# ecu2.net
KiCad netlist of a schematic drawn in EAGLE
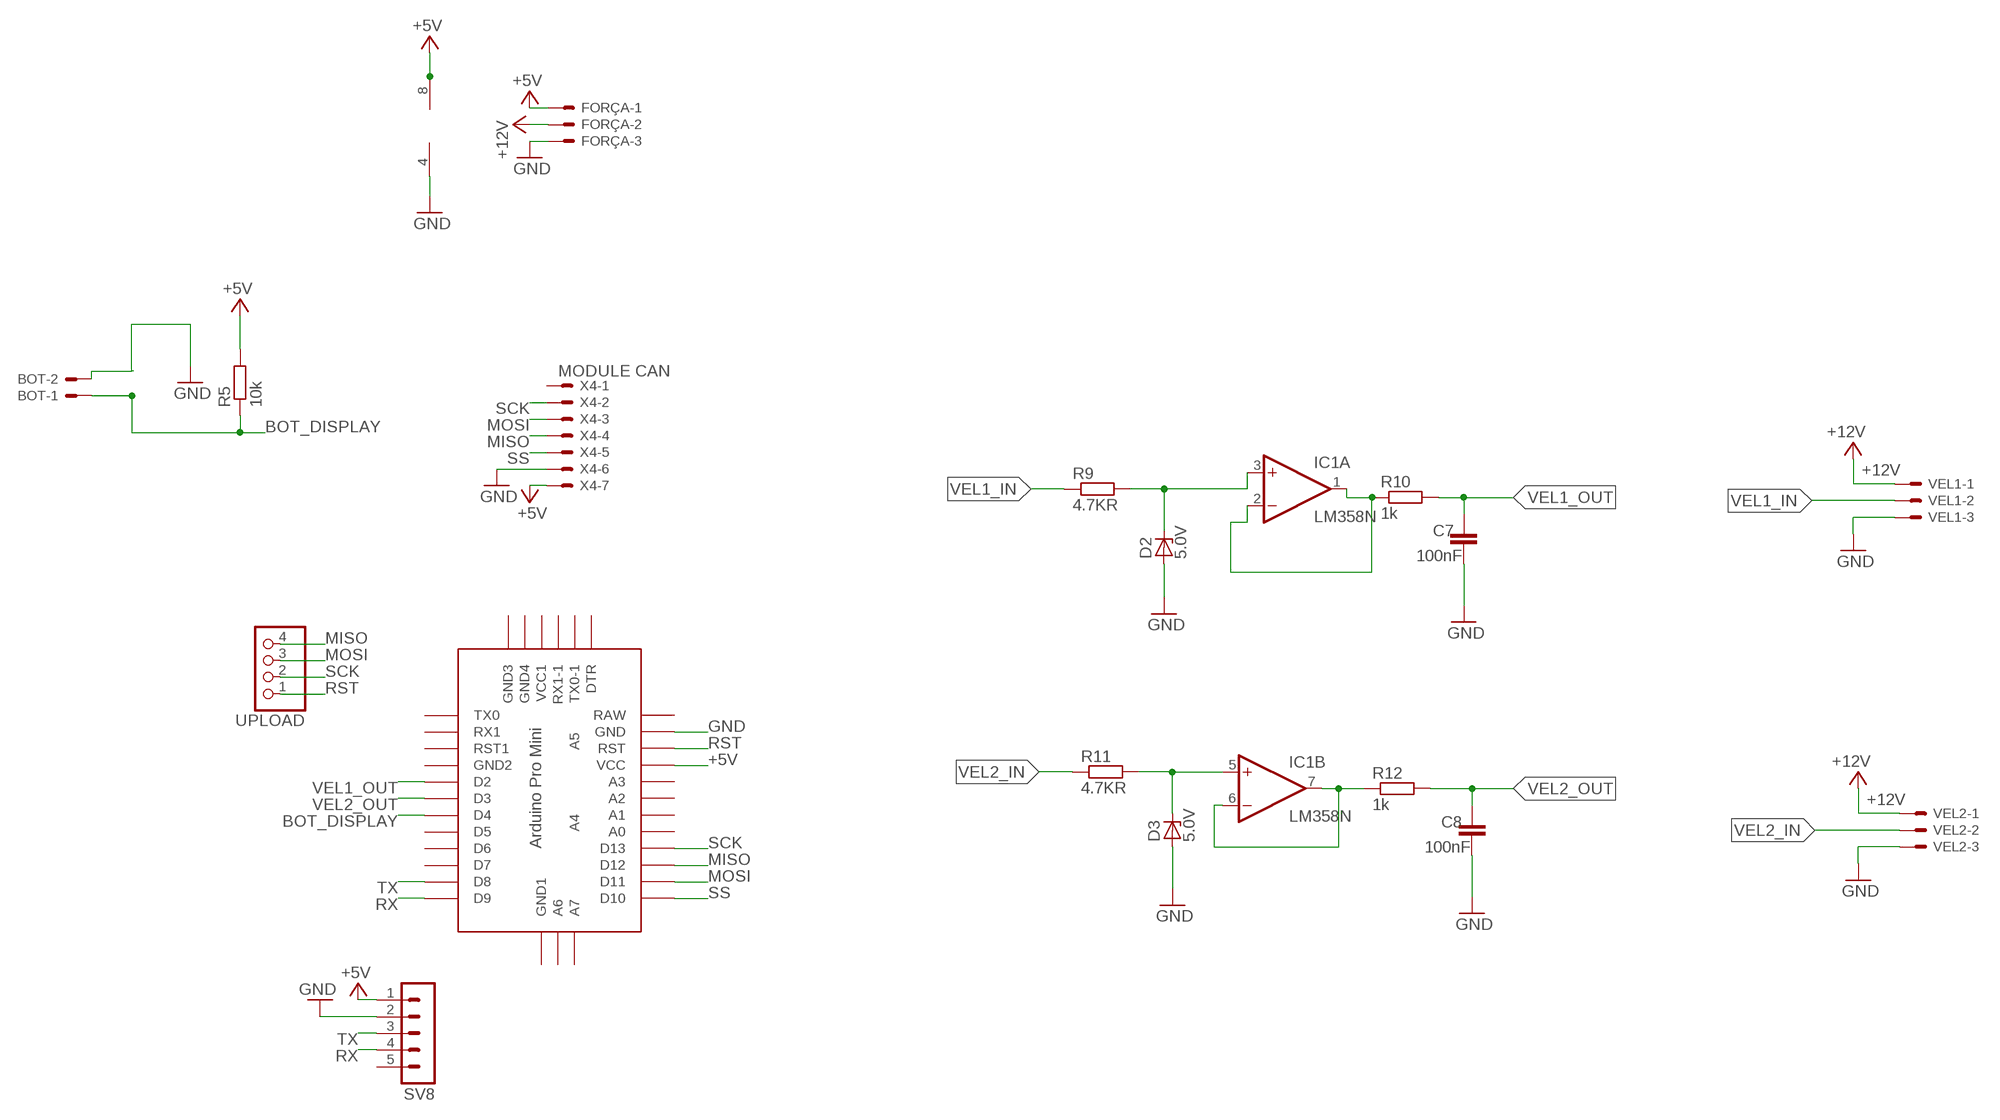
[diagram p0: schematic, sheet 1]

(export (version "E")
  (design (tool "Eeschema 10.0.6"))
  (components
    (comp (ref "BOT")
      (value "RPM")
      (footprint "eagle-import:22-23-2021")
      (fields (field (name "MF") "MOLEX") (field (name "MPN") "22-23-2021"))
      (libsource (lib "eagle-import") (part "22-23-2021"))
    )
    (comp (ref "C7")
      (value "100nF")
      (footprint "eagle-import:C5B2.5")
      (libsource (lib "eagle-import") (part "C5/2.5"))
    )
    (comp (ref "C8")
      (value "100nF")
      (footprint "eagle-import:C5B2.5")
      (libsource (lib "eagle-import") (part "C5/2.5"))
    )
    (comp (ref "D2")
      (value "5.0V")
      (footprint "eagle-import:DO34Z7")
      (libsource (lib "eagle-import") (part "ZENER-DIODEDO34-7"))
    )
    (comp (ref "D3")
      (value "5.0V")
      (footprint "eagle-import:DO34Z7")
      (libsource (lib "eagle-import") (part "ZENER-DIODEDO34-7"))
    )
    (comp (ref "FORÇA")
      (value "FORÇA")
      (footprint "eagle-import:22-23-2031")
      (fields (field (name "MF") "MOLEX") (field (name "MPN") "22-23-2031"))
      (libsource (lib "eagle-import") (part "22-23-2031"))
    )
    (comp (ref "IC1")
      (value "LM358N")
      (footprint "eagle-import:DIL08")
      (libsource (lib "eagle-import") (part "LM358N"))
    )
    (comp (ref "R5")
      (value "10k")
      (footprint "eagle-import:0207_7")
      (libsource (lib "eagle-import") (part "R-EU_0207/7"))
    )
    (comp (ref "R9")
      (value "4.7KR")
      (footprint "eagle-import:0207_7")
      (libsource (lib "eagle-import") (part "R-EU_0207/7"))
    )
    (comp (ref "R10")
      (value "1k")
      (footprint "eagle-import:0207_7")
      (libsource (lib "eagle-import") (part "R-EU_0207/7"))
    )
    (comp (ref "R11")
      (value "4.7KR")
      (footprint "eagle-import:0207_7")
      (libsource (lib "eagle-import") (part "R-EU_0207/7"))
    )
    (comp (ref "R12")
      (value "1k")
      (footprint "eagle-import:0207_7")
      (libsource (lib "eagle-import") (part "R-EU_0207/7"))
    )
    (comp (ref "SV8")
      (value "MA05-1")
      (footprint "eagle-import:MA05-1")
      (libsource (lib "eagle-import") (part "MA05-1"))
    )
    (comp (ref "U$1")
      (value "ABK-PRO-MINI")
      (footprint "eagle-import:ABK-PRO-MINI")
      (libsource (lib "eagle-import") (part "ABK-PRO-MINI"))
    )
    (comp (ref "UPLOAD")
      (value "PINHD-1X4")
      (footprint "eagle-import:1X04")
      (libsource (lib "eagle-import") (part "PINHD-1X4"))
    )
    (comp (ref "VEL1")
      (value "COMB 1")
      (footprint "eagle-import:22-23-2031")
      (fields (field (name "MF") "MOLEX") (field (name "MPN") "22-23-2031"))
      (libsource (lib "eagle-import") (part "22-23-2031"))
    )
    (comp (ref "VEL2")
      (value "COMB 2")
      (footprint "eagle-import:22-23-2031")
      (fields (field (name "MF") "MOLEX") (field (name "MPN") "22-23-2031"))
      (libsource (lib "eagle-import") (part "22-23-2031"))
    )
    (comp (ref "X4")
      (value "MODULE CAN")
      (footprint "eagle-import:22-23-2071")
      (fields (field (name "MF") "MOLEX") (field (name "MPN") "22-23-2071"))
      (libsource (lib "eagle-import") (part "22-23-2071"))
    )
  )
  (nets
    (net (code "1") (name "+5V") (class "Default")
      (node (ref "FORÇA") (pin "1") (pinfunction "S_1") (pintype "passive"))
      (node (ref "IC1") (pin "8") (pinfunction "V+_8") (pintype "power_in"))
      (node (ref "R5") (pin "2") (pinfunction "2_2") (pintype "passive"))
      (node (ref "SV8") (pin "1") (pinfunction "1_1") (pintype "passive"))
      (node (ref "U$1") (pin "VCC") (pinfunction "VCC_VCC") (pintype "bidirectional"))
      (node (ref "X4") (pin "7") (pinfunction "S_7") (pintype "passive"))
    )
    (net (code "2") (name "+12V") (class "Default")
      (node (ref "FORÇA") (pin "2") (pinfunction "S_2") (pintype "passive"))
      (node (ref "VEL1") (pin "1") (pinfunction "S_1") (pintype "passive"))
      (node (ref "VEL2") (pin "1") (pinfunction "S_1") (pintype "passive"))
    )
    (net (code "3") (name "/BOT_DISPLAY") (class "Default")
      (node (ref "BOT") (pin "1") (pinfunction "S_1") (pintype "passive"))
      (node (ref "R5") (pin "1") (pinfunction "1_1") (pintype "passive"))
      (node (ref "U$1") (pin "D4") (pinfunction "D4_D4") (pintype "bidirectional"))
    )
    (net (code "4") (name "/MISO") (class "Default")
      (node (ref "U$1") (pin "D12") (pinfunction "D12_D12") (pintype "bidirectional"))
      (node (ref "UPLOAD") (pin "4") (pinfunction "4_4") (pintype "passive"))
      (node (ref "X4") (pin "4") (pinfunction "S_4") (pintype "passive"))
    )
    (net (code "5") (name "/MOSI") (class "Default")
      (node (ref "U$1") (pin "D11") (pinfunction "D11_D11") (pintype "bidirectional"))
      (node (ref "UPLOAD") (pin "3") (pinfunction "3_3") (pintype "passive"))
      (node (ref "X4") (pin "3") (pinfunction "S_3") (pintype "passive"))
    )
    (net (code "6") (name "/RST") (class "Default")
      (node (ref "U$1") (pin "RST") (pinfunction "RST_RST") (pintype "bidirectional"))
      (node (ref "UPLOAD") (pin "1") (pinfunction "1_1") (pintype "passive"))
    )
    (net (code "7") (name "/RX") (class "Default")
      (node (ref "SV8") (pin "4") (pinfunction "4_4") (pintype "passive"))
      (node (ref "U$1") (pin "D9") (pinfunction "D9_D9") (pintype "bidirectional"))
    )
    (net (code "8") (name "/SCK") (class "Default")
      (node (ref "U$1") (pin "D13") (pinfunction "D13_D13") (pintype "bidirectional"))
      (node (ref "UPLOAD") (pin "2") (pinfunction "2_2") (pintype "passive"))
      (node (ref "X4") (pin "2") (pinfunction "S_2") (pintype "passive"))
    )
    (net (code "9") (name "/SS") (class "Default")
      (node (ref "U$1") (pin "D10") (pinfunction "D10_D10") (pintype "bidirectional"))
      (node (ref "X4") (pin "5") (pinfunction "S_5") (pintype "passive"))
    )
    (net (code "10") (name "/TX") (class "Default")
      (node (ref "SV8") (pin "3") (pinfunction "3_3") (pintype "passive"))
      (node (ref "U$1") (pin "D8") (pinfunction "D8_D8") (pintype "bidirectional"))
    )
    (net (code "11") (name "GND") (class "Default")
      (node (ref "BOT") (pin "2") (pinfunction "S_2") (pintype "passive"))
      (node (ref "C7") (pin "1") (pinfunction "1_1") (pintype "passive"))
      (node (ref "C8") (pin "1") (pinfunction "1_1") (pintype "passive"))
      (node (ref "D2") (pin "A") (pinfunction "A_A") (pintype "passive"))
      (node (ref "D3") (pin "A") (pinfunction "A_A") (pintype "passive"))
      (node (ref "FORÇA") (pin "3") (pinfunction "S_3") (pintype "passive"))
      (node (ref "IC1") (pin "4") (pinfunction "V-_4") (pintype "power_in"))
      (node (ref "SV8") (pin "2") (pinfunction "2_2") (pintype "passive"))
      (node (ref "U$1") (pin "GND") (pinfunction "GND_GND") (pintype "bidirectional"))
      (node (ref "VEL1") (pin "3") (pinfunction "S_3") (pintype "passive"))
      (node (ref "VEL2") (pin "3") (pinfunction "S_3") (pintype "passive"))
      (node (ref "X4") (pin "6") (pinfunction "S_6") (pintype "passive"))
    )
    (net (code "12") (name "Net-(IC1A-+IN)") (class "Default")
      (node (ref "D2") (pin "C") (pinfunction "C_C") (pintype "passive"))
      (node (ref "IC1") (pin "3") (pinfunction "+IN_3") (pintype "input"))
      (node (ref "R9") (pin "2") (pinfunction "2_2") (pintype "passive"))
    )
    (net (code "13") (name "Net-(IC1A--IN)") (class "Default")
      (node (ref "IC1") (pin "1") (pinfunction "OUT_1") (pintype "output"))
      (node (ref "IC1") (pin "2") (pinfunction "-IN_2") (pintype "input"))
      (node (ref "R10") (pin "1") (pinfunction "1_1") (pintype "passive"))
    )
    (net (code "14") (name "Net-(IC1B-+IN)") (class "Default")
      (node (ref "D3") (pin "C") (pinfunction "C_C") (pintype "passive"))
      (node (ref "IC1") (pin "5") (pinfunction "+IN_5") (pintype "input"))
      (node (ref "R11") (pin "2") (pinfunction "2_2") (pintype "passive"))
    )
    (net (code "15") (name "Net-(IC1B--IN)") (class "Default")
      (node (ref "IC1") (pin "6") (pinfunction "-IN_6") (pintype "input"))
      (node (ref "IC1") (pin "7") (pinfunction "OUT_7") (pintype "output"))
      (node (ref "R12") (pin "1") (pinfunction "1_1") (pintype "passive"))
    )
    (net (code "16") (name "VEL1_IN") (class "Default")
      (node (ref "R9") (pin "1") (pinfunction "1_1") (pintype "passive"))
      (node (ref "VEL1") (pin "2") (pinfunction "S_2") (pintype "passive"))
    )
    (net (code "17") (name "VEL1_OUT") (class "Default")
      (node (ref "C7") (pin "2") (pinfunction "2_2") (pintype "passive"))
      (node (ref "R10") (pin "2") (pinfunction "2_2") (pintype "passive"))
      (node (ref "U$1") (pin "D2") (pinfunction "D2_D2") (pintype "bidirectional"))
    )
    (net (code "18") (name "VEL2_IN") (class "Default")
      (node (ref "R11") (pin "1") (pinfunction "1_1") (pintype "passive"))
      (node (ref "VEL2") (pin "2") (pinfunction "S_2") (pintype "passive"))
    )
    (net (code "19") (name "VEL2_OUT") (class "Default")
      (node (ref "C8") (pin "2") (pinfunction "2_2") (pintype "passive"))
      (node (ref "R12") (pin "2") (pinfunction "2_2") (pintype "passive"))
      (node (ref "U$1") (pin "D3") (pinfunction "D3_D3") (pintype "bidirectional"))
    )
    (net (code "20") (name "unconnected-(SV8-Pad5)") (class "Default")
      (node (ref "SV8") (pin "5") (pinfunction "5_5") (pintype "passive"))
    )
    (net (code "21") (name "unconnected-(U$1-GND1-PadGND4)") (class "Default")
      (node (ref "U$1") (pin "GND4") (pinfunction "GND1_GND4") (pintype "bidirectional"))
    )
    (net (code "22") (name "unconnected-(U$1-GND2-PadGND1)") (class "Default")
      (node (ref "U$1") (pin "GND1") (pinfunction "GND2_GND1") (pintype "bidirectional"))
    )
    (net (code "23") (name "unconnected-(U$1-GND3-PadGND2)") (class "Default")
      (node (ref "U$1") (pin "GND2") (pinfunction "GND3_GND2") (pintype "bidirectional"))
    )
    (net (code "24") (name "unconnected-(U$1-GND4-PadGND3)") (class "Default")
      (node (ref "U$1") (pin "GND3") (pinfunction "GND4_GND3") (pintype "bidirectional"))
    )
    (net (code "25") (name "unconnected-(U$1-PadA0)") (class "Default")
      (node (ref "U$1") (pin "A0") (pinfunction "A0_A0") (pintype "bidirectional"))
    )
    (net (code "26") (name "unconnected-(U$1-PadA1)") (class "Default")
      (node (ref "U$1") (pin "A1") (pinfunction "A1_A1") (pintype "bidirectional"))
    )
    (net (code "27") (name "unconnected-(U$1-PadA2)") (class "Default")
      (node (ref "U$1") (pin "A2") (pinfunction "A2_A2") (pintype "bidirectional"))
    )
    (net (code "28") (name "unconnected-(U$1-PadA3)") (class "Default")
      (node (ref "U$1") (pin "A3") (pinfunction "A3_A3") (pintype "bidirectional"))
    )
    (net (code "29") (name "unconnected-(U$1-PadA4)") (class "Default")
      (node (ref "U$1") (pin "A4") (pinfunction "A4_A4") (pintype "bidirectional"))
    )
    (net (code "30") (name "unconnected-(U$1-PadA5)") (class "Default")
      (node (ref "U$1") (pin "A5") (pinfunction "A5_A5") (pintype "bidirectional"))
    )
    (net (code "31") (name "unconnected-(U$1-PadA6)") (class "Default")
      (node (ref "U$1") (pin "A6") (pinfunction "A6_A6") (pintype "bidirectional"))
    )
    (net (code "32") (name "unconnected-(U$1-PadA7)") (class "Default")
      (node (ref "U$1") (pin "A7") (pinfunction "A7_A7") (pintype "bidirectional"))
    )
    (net (code "33") (name "unconnected-(U$1-PadD5)") (class "Default")
      (node (ref "U$1") (pin "D5") (pinfunction "D5_D5") (pintype "bidirectional"))
    )
    (net (code "34") (name "unconnected-(U$1-PadD6)") (class "Default")
      (node (ref "U$1") (pin "D6") (pinfunction "D6_D6") (pintype "bidirectional"))
    )
    (net (code "35") (name "unconnected-(U$1-PadD7)") (class "Default")
      (node (ref "U$1") (pin "D7") (pinfunction "D7_D7") (pintype "bidirectional"))
    )
    (net (code "36") (name "unconnected-(U$1-PadDTR)") (class "Default")
      (node (ref "U$1") (pin "DTR") (pinfunction "DTR_DTR") (pintype "bidirectional"))
    )
    (net (code "37") (name "unconnected-(U$1-PadRAW)") (class "Default")
      (node (ref "U$1") (pin "RAW") (pinfunction "RAW_RAW") (pintype "bidirectional"))
    )
    (net (code "38") (name "unconnected-(U$1-PadRST1)") (class "Default")
      (node (ref "U$1") (pin "RST1") (pinfunction "RST1_RST1") (pintype "bidirectional"))
    )
    (net (code "39") (name "unconnected-(U$1-PadRX1)") (class "Default")
      (node (ref "U$1") (pin "RX1") (pinfunction "RX1_RX1") (pintype "bidirectional"))
    )
    (net (code "40") (name "unconnected-(U$1-PadRX1-1)") (class "Default")
      (node (ref "U$1") (pin "RX1-1") (pinfunction "RX1-1_RX1-1") (pintype "bidirectional"))
    )
    (net (code "41") (name "unconnected-(U$1-PadTX0)") (class "Default")
      (node (ref "U$1") (pin "TX0") (pinfunction "TX0_TX0") (pintype "bidirectional"))
    )
    (net (code "42") (name "unconnected-(U$1-PadTX0-1)") (class "Default")
      (node (ref "U$1") (pin "TX0-1") (pinfunction "TX0-1_TX0-1") (pintype "bidirectional"))
    )
    (net (code "43") (name "unconnected-(U$1-PadVCC1)") (class "Default")
      (node (ref "U$1") (pin "VCC1") (pinfunction "VCC1_VCC1") (pintype "bidirectional"))
    )
    (net (code "44") (name "unconnected-(X4A-S-Pad1)") (class "Default")
      (node (ref "X4") (pin "1") (pinfunction "S_1") (pintype "passive"))
    )
  )
)
